# Schematic_Livestock_control_and_monitori.net
KiCad netlist of a schematic drawn in Altium Designer
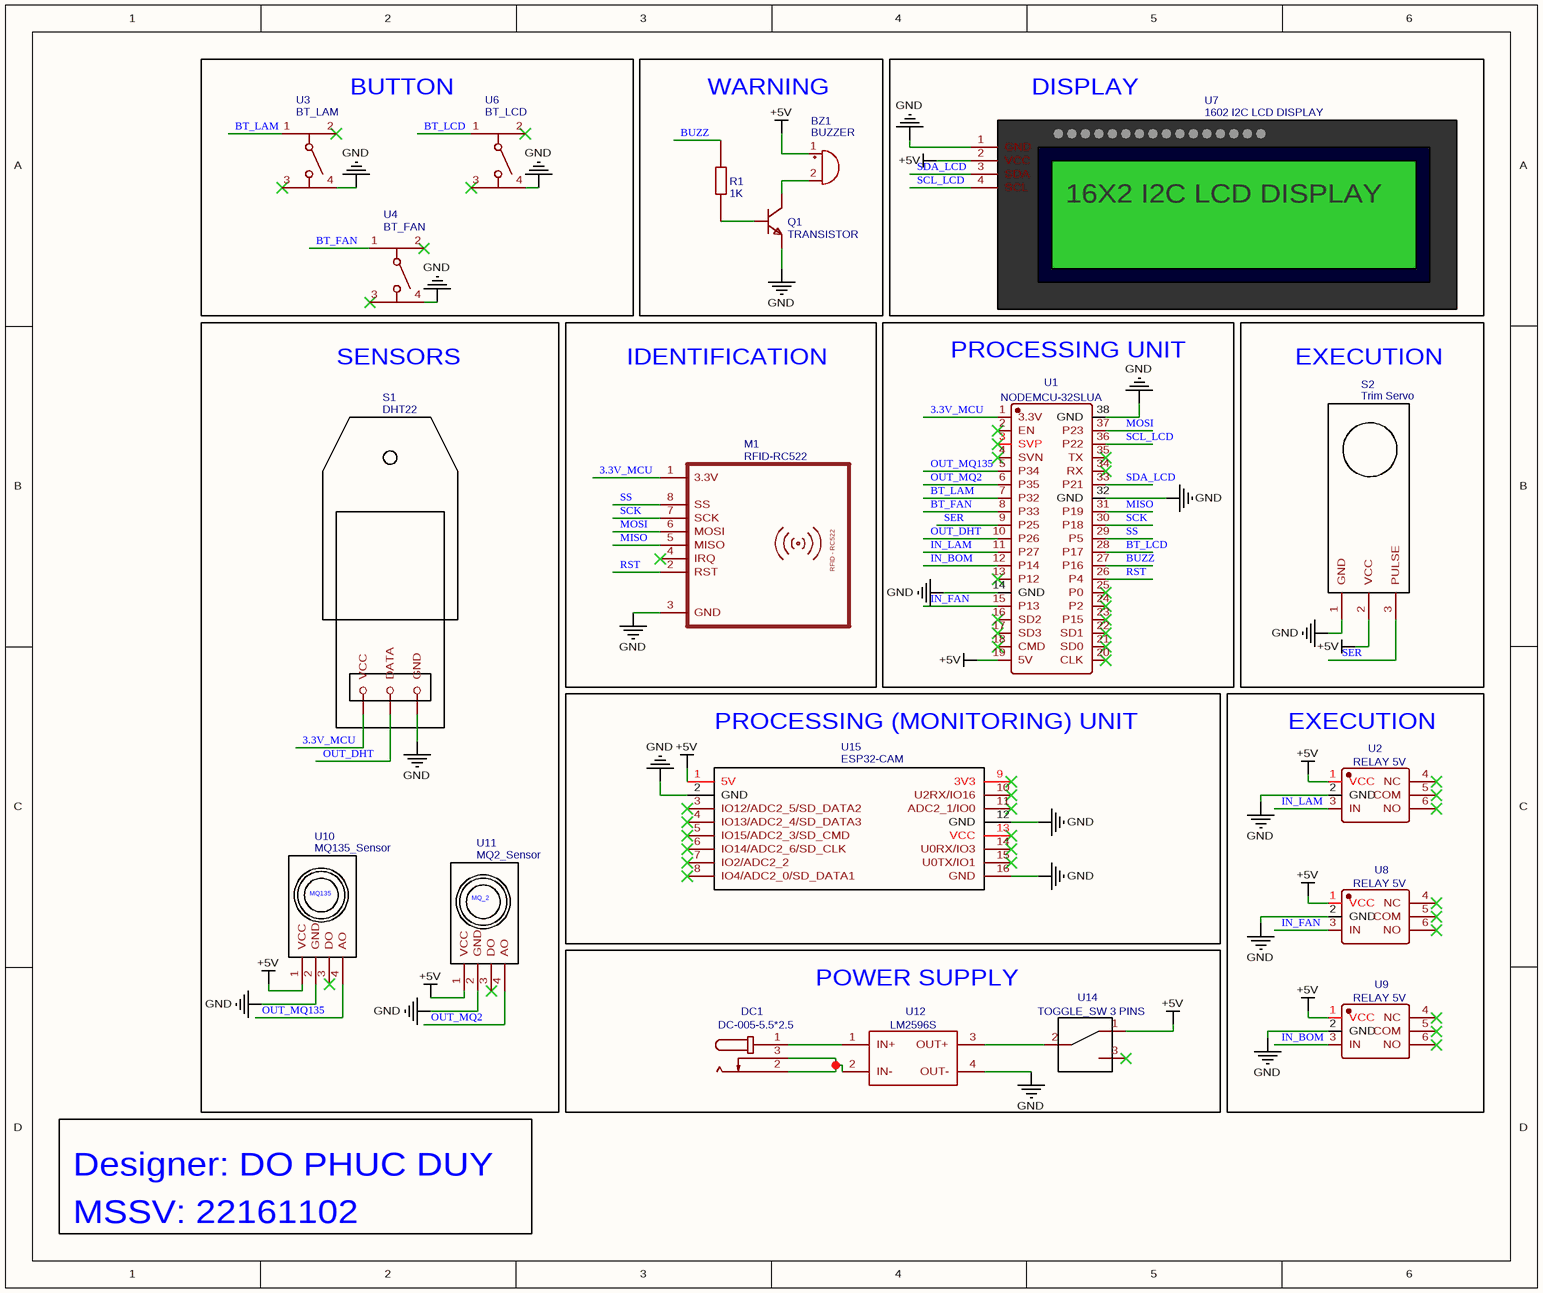
[diagram p0: Schematic_Livestock control and monitoring system.schdoc]

(export (version "E")
  (design (tool "Eeschema 10.0.6"))
  (components
    (comp (ref "BZ1")
      (value "BUZZER")
      (fields (field (name "CONTRIBUTOR") "xuantan27012003"))
      (libsource (lib "altium-import") (part "root_0_BUZZER_"))
    )
    (comp (ref "DC1")
      (value "DC-005-5.5*2.5")
      (fields (field (name "CONTRIBUTOR") "lcsc"))
      (libsource (lib "altium-import") (part "root_0_DC-005-5.5*2.5_"))
    )
    (comp (ref "M1")
      (value "RFID-RC522")
      (fields (field (name "CONTRIBUTOR") "manthan_0182"))
      (libsource (lib "altium-import") (part "root_0_RFID-RC522_"))
    )
    (comp (ref "Q1")
      (value "TRANSISTOR")
      (fields
        (field (name "MANUFACTURER") "SEMTECH")
        (field (name "MANUFACTURER PART") "2N4401")
        (field (name "CONTRIBUTOR") "ali.sivananda")
      )
      (libsource (lib "altium-import") (part "root_0_TRANSISTOR_"))
    )
    (comp (ref "R1")
      (value "1K")
      (fields
        (field (name "MANUFACTURER") "Multicomp")
        (field (name "MANUFACTURER PART") "MOR01SJ0101A10")
        (field (name "CONTRIBUTOR") "Isuru Sandaruwan")
      )
      (libsource (lib "altium-import") (part "root_1_1K_"))
    )
    (comp (ref "S1")
      (value "DHT22")
      (fields (field (name "CONTRIBUTOR") "Muhammad Taufiq"))
      (libsource (lib "altium-import") (part "root_1_DHT22_"))
    )
    (comp (ref "S2")
      (value "Trim Servo")
      (fields (field (name "CONTRIBUTOR") "Sunil Sinsinwar"))
      (libsource (lib "altium-import") (part "root_0_Trim Servo_"))
    )
    (comp (ref "U1")
      (value "NODEMCU-32SLUA")
      (fields
        (field (name "MANUFACTURER") "Ai-Thinker(安信可)")
        (field (name "MANUFACTURER PART") "NodeMCU-32SLua")
        (field (name "CONTRIBUTOR") "lcsc")
      )
      (libsource (lib "altium-import") (part "root_0_NODEMCU-32SLUA_"))
    )
    (comp (ref "U2")
      (value "RELAY 5V")
      (fields
        (field (name "MANUFACTURER") "China")
        (field (name "MANUFACTURER PART") "Monday Kids")
        (field (name "CONTRIBUTOR") "dophucduy3")
      )
      (libsource (lib "altium-import") (part "root_0_RELAY 5V_"))
    )
    (comp (ref "U3")
      (value "BT_LAM")
      (fields
        (field (name "MANUFACTURER") "BBJ")
        (field (name "MANUFACTURER PART") "Switch,6*6*6Plastic head,260G, 0.25mm,Straight line")
      )
      (libsource (lib "altium-import") (part "root_0_BT_LAM_"))
    )
    (comp (ref "U4")
      (value "BT_FAN")
      (fields
        (field (name "MANUFACTURER") "BBJ")
        (field (name "MANUFACTURER PART") "Switch,6*6*6Plastic head,260G, 0.25mm,Straight line")
      )
      (libsource (lib "altium-import") (part "root_0_BT_FAN_"))
    )
    (comp (ref "U6")
      (value "BT_LCD")
      (fields
        (field (name "MANUFACTURER") "BBJ")
        (field (name "MANUFACTURER PART") "Switch,6*6*6Plastic head,260G, 0.25mm,Straight line")
      )
      (libsource (lib "altium-import") (part "root_0_BT_LCD_"))
    )
    (comp (ref "U7")
      (value "1602 I2C LCD DISPLAY")
      (fields (field (name "CONTRIBUTOR") "dophucduy3"))
      (libsource (lib "altium-import") (part "root_0_1602 I2C LCD DISPLAY_"))
    )
    (comp (ref "U8")
      (value "RELAY 5V")
      (fields
        (field (name "MANUFACTURER") "China")
        (field (name "MANUFACTURER PART") "Monday Kids")
        (field (name "CONTRIBUTOR") "dophucduy3")
      )
      (libsource (lib "altium-import") (part "root_0_RELAY 5V_"))
    )
    (comp (ref "U9")
      (value "RELAY 5V")
      (fields
        (field (name "MANUFACTURER") "China")
        (field (name "MANUFACTURER PART") "Monday Kids")
        (field (name "CONTRIBUTOR") "dophucduy3")
      )
      (libsource (lib "altium-import") (part "root_0_RELAY 5V_"))
    )
    (comp (ref "U10")
      (value "MQ135_Sensor")
      (fields (field (name "CONTRIBUTOR") "rusiru5707"))
      (libsource (lib "altium-import") (part "root_0_MQ135_Sensor_"))
    )
    (comp (ref "U11")
      (value "MQ2_Sensor")
      (fields (field (name "CONTRIBUTOR") "rusiru5707"))
      (libsource (lib "altium-import") (part "root_0_MQ2_Sensor_"))
    )
    (comp (ref "U12")
      (value "LM2596S")
      (description "Servo 5V")
      (fields (field (name "CONTRIBUTOR") "mannymoy86"))
      (libsource (lib "altium-import") (part "root_0_LM2596S_"))
    )
    (comp (ref "U14")
      (value "TOGGLE_SW 3 PINS")
      (fields (field (name "CONTRIBUTOR") "cesaro.patafisico"))
      (libsource (lib "altium-import") (part "root_0_TOGGLE_SW 3 PINS_"))
    )
    (comp (ref "U15")
      (value "ESP32-CAM")
      (fields (field (name "CONTRIBUTOR") "dophucduy3"))
      (libsource (lib "altium-import") (part "root_0_ESP32-CAM_"))
    )
  )
  (nets
    (net (code "1") (name "+5V") (class "Default")
      (node (ref "BZ1") (pin "1") (pinfunction "+_1") (pintype "passive"))
      (node (ref "S2") (pin "2") (pinfunction "VCC_2") (pintype "passive"))
      (node (ref "U1") (pin "19") (pinfunction "5V_19") (pintype "passive"))
      (node (ref "U10") (pin "1") (pinfunction "VCC_1") (pintype "passive"))
      (node (ref "U11") (pin "1") (pinfunction "VCC_1") (pintype "passive"))
      (node (ref "U14") (pin "1") (pinfunction "1_1") (pintype "passive"))
      (node (ref "U15") (pin "1") (pinfunction "5V_1") (pintype "passive"))
      (node (ref "U2") (pin "1") (pinfunction "VCC_1") (pintype "passive"))
      (node (ref "U7") (pin "2") (pinfunction "VCC_2") (pintype "passive"))
      (node (ref "U8") (pin "1") (pinfunction "VCC_1") (pintype "passive"))
      (node (ref "U9") (pin "1") (pinfunction "VCC_1") (pintype "passive"))
    )
    (net (code "2") (name "/3.3V_MCU") (class "Default")
      (node (ref "M1") (pin "1") (pinfunction "3.3V_1") (pintype "passive"))
      (node (ref "S1") (pin "1") (pinfunction "VCC_1") (pintype "passive"))
      (node (ref "U1") (pin "1") (pinfunction "3.3V_1") (pintype "passive"))
    )
    (net (code "3") (name "/BT_FAN") (class "Default")
      (node (ref "U1") (pin "8") (pinfunction "P33_8") (pintype "passive"))
      (node (ref "U4") (pin "1") (pinfunction "1_1") (pintype "passive"))
    )
    (net (code "4") (name "/BT_LAM") (class "Default")
      (node (ref "U1") (pin "7") (pinfunction "P32_7") (pintype "passive"))
      (node (ref "U3") (pin "1") (pinfunction "1_1") (pintype "passive"))
    )
    (net (code "5") (name "/BT_LCD") (class "Default")
      (node (ref "U1") (pin "28") (pinfunction "P17_28") (pintype "passive"))
      (node (ref "U6") (pin "1") (pinfunction "1_1") (pintype "passive"))
    )
    (net (code "6") (name "/BUZZ") (class "Default")
      (node (ref "R1") (pin "2") (pinfunction "2_2") (pintype "passive"))
      (node (ref "U1") (pin "27") (pinfunction "P16_27") (pintype "passive"))
    )
    (net (code "7") (name "/IN_BOM") (class "Default")
      (node (ref "U1") (pin "12") (pinfunction "P14_12") (pintype "passive"))
      (node (ref "U9") (pin "3") (pinfunction "IN_3") (pintype "passive"))
    )
    (net (code "8") (name "/IN_FAN") (class "Default")
      (node (ref "U1") (pin "15") (pinfunction "P13_15") (pintype "passive"))
      (node (ref "U8") (pin "3") (pinfunction "IN_3") (pintype "passive"))
    )
    (net (code "9") (name "/IN_LAM") (class "Default")
      (node (ref "U1") (pin "11") (pinfunction "P27_11") (pintype "passive"))
      (node (ref "U2") (pin "3") (pinfunction "IN_3") (pintype "passive"))
    )
    (net (code "10") (name "/MISO") (class "Default")
      (node (ref "M1") (pin "5") (pinfunction "MISO_5") (pintype "passive"))
      (node (ref "U1") (pin "31") (pinfunction "P19_31") (pintype "passive"))
    )
    (net (code "11") (name "/MOSI") (class "Default")
      (node (ref "M1") (pin "6") (pinfunction "MOSI_6") (pintype "passive"))
      (node (ref "U1") (pin "37") (pinfunction "P23_37") (pintype "passive"))
    )
    (net (code "12") (name "/OUT_DHT") (class "Default")
      (node (ref "S1") (pin "2") (pinfunction "DATA_2") (pintype "passive"))
      (node (ref "U1") (pin "10") (pinfunction "P26_10") (pintype "passive"))
    )
    (net (code "13") (name "/OUT_MQ2") (class "Default")
      (node (ref "U1") (pin "6") (pinfunction "P35_6") (pintype "passive"))
      (node (ref "U11") (pin "4") (pinfunction "AO_4") (pintype "passive"))
    )
    (net (code "14") (name "/OUT_MQ135") (class "Default")
      (node (ref "U1") (pin "5") (pinfunction "P34_5") (pintype "passive"))
      (node (ref "U10") (pin "4") (pinfunction "AO_4") (pintype "passive"))
    )
    (net (code "15") (name "/RST") (class "Default")
      (node (ref "M1") (pin "2") (pinfunction "RST_2") (pintype "passive"))
      (node (ref "U1") (pin "26") (pinfunction "P4_26") (pintype "passive"))
    )
    (net (code "16") (name "/SCK") (class "Default")
      (node (ref "M1") (pin "7") (pinfunction "SCK_7") (pintype "passive"))
      (node (ref "U1") (pin "30") (pinfunction "P18_30") (pintype "passive"))
    )
    (net (code "17") (name "/SCL_LCD") (class "Default")
      (node (ref "U1") (pin "36") (pinfunction "P22_36") (pintype "passive"))
      (node (ref "U7") (pin "4") (pinfunction "SCL_4") (pintype "passive"))
    )
    (net (code "18") (name "/SDA_LCD") (class "Default")
      (node (ref "U1") (pin "33") (pinfunction "P21_33") (pintype "passive"))
      (node (ref "U7") (pin "3") (pinfunction "SDA_3") (pintype "passive"))
    )
    (net (code "19") (name "/SER") (class "Default")
      (node (ref "S2") (pin "3") (pinfunction "PULSE_3") (pintype "passive"))
      (node (ref "U1") (pin "9") (pinfunction "P25_9") (pintype "passive"))
    )
    (net (code "20") (name "/SS") (class "Default")
      (node (ref "M1") (pin "8") (pinfunction "SS_8") (pintype "passive"))
      (node (ref "U1") (pin "29") (pinfunction "P5_29") (pintype "passive"))
    )
    (net (code "21") (name "GND") (class "Default")
      (node (ref "M1") (pin "3") (pinfunction "GND_3") (pintype "passive"))
      (node (ref "Q1") (pin "1") (pinfunction "E_1") (pintype "passive"))
      (node (ref "S1") (pin "3") (pinfunction "GND_3") (pintype "passive"))
      (node (ref "S2") (pin "1") (pinfunction "GND_1") (pintype "passive"))
      (node (ref "U1") (pin "14") (pinfunction "GND_14") (pintype "passive"))
      (node (ref "U1") (pin "32") (pinfunction "GND_32") (pintype "passive"))
      (node (ref "U1") (pin "38") (pinfunction "GND_38") (pintype "passive"))
      (node (ref "U10") (pin "2") (pinfunction "GND_2") (pintype "passive"))
      (node (ref "U11") (pin "2") (pinfunction "GND_2") (pintype "passive"))
      (node (ref "U12") (pin "4") (pinfunction "OUT-_4") (pintype "passive"))
      (node (ref "U15") (pin "12") (pinfunction "GND_12") (pintype "passive"))
      (node (ref "U15") (pin "16") (pinfunction "GND_16") (pintype "passive"))
      (node (ref "U15") (pin "2") (pinfunction "GND_2") (pintype "passive"))
      (node (ref "U2") (pin "2") (pinfunction "GND_2") (pintype "passive"))
      (node (ref "U3") (pin "4") (pinfunction "4_4") (pintype "passive"))
      (node (ref "U4") (pin "4") (pinfunction "4_4") (pintype "passive"))
      (node (ref "U6") (pin "4") (pinfunction "4_4") (pintype "passive"))
      (node (ref "U7") (pin "1") (pinfunction "GND_1") (pintype "passive"))
      (node (ref "U8") (pin "2") (pinfunction "GND_2") (pintype "passive"))
      (node (ref "U9") (pin "2") (pinfunction "GND_2") (pintype "passive"))
    )
    (net (code "22") (name "Net-(BZ1--)") (class "Default")
      (node (ref "BZ1") (pin "2") (pinfunction "-_2") (pintype "passive"))
      (node (ref "Q1") (pin "3") (pinfunction "C_3") (pintype "passive"))
    )
    (net (code "23") (name "Net-(Q1-B)") (class "Default")
      (node (ref "Q1") (pin "2") (pinfunction "B_2") (pintype "passive"))
      (node (ref "R1") (pin "1") (pinfunction "1_1") (pintype "passive"))
    )
    (net (code "24") (name "Net-(U12-IN+)") (class "Default")
      (node (ref "DC1") (pin "1") (pinfunction "1_1") (pintype "passive"))
      (node (ref "U12") (pin "1") (pinfunction "IN+_1") (pintype "passive"))
    )
    (net (code "25") (name "Net-(U12-IN-)") (class "Default")
      (node (ref "DC1") (pin "2") (pinfunction "2_2") (pintype "passive"))
      (node (ref "DC1") (pin "3") (pinfunction "3_3") (pintype "passive"))
      (node (ref "U12") (pin "2") (pinfunction "IN-_2") (pintype "passive"))
    )
    (net (code "26") (name "Net-(U12-OUT+)") (class "Default")
      (node (ref "U12") (pin "3") (pinfunction "OUT+_3") (pintype "passive"))
      (node (ref "U14") (pin "2") (pinfunction "2_2") (pintype "passive"))
    )
    (net (code "27") (name "unconnected-(M1-IRQ-Pad4)") (class "Default")
      (node (ref "M1") (pin "4") (pinfunction "IRQ_4") (pintype "passive+no_connect"))
    )
    (net (code "28") (name "unconnected-(U1-CLK-Pad20)") (class "Default")
      (node (ref "U1") (pin "20") (pinfunction "CLK_20") (pintype "passive+no_connect"))
    )
    (net (code "29") (name "unconnected-(U1-CMD-Pad18)") (class "Default")
      (node (ref "U1") (pin "18") (pinfunction "CMD_18") (pintype "passive+no_connect"))
    )
    (net (code "30") (name "unconnected-(U1-EN-Pad2)") (class "Default")
      (node (ref "U1") (pin "2") (pinfunction "EN_2") (pintype "passive+no_connect"))
    )
    (net (code "31") (name "unconnected-(U1-P0-Pad25)") (class "Default")
      (node (ref "U1") (pin "25") (pinfunction "P0_25") (pintype "passive+no_connect"))
    )
    (net (code "32") (name "unconnected-(U1-P2-Pad24)") (class "Default")
      (node (ref "U1") (pin "24") (pinfunction "P2_24") (pintype "passive+no_connect"))
    )
    (net (code "33") (name "unconnected-(U1-P12-Pad13)") (class "Default")
      (node (ref "U1") (pin "13") (pinfunction "P12_13") (pintype "passive+no_connect"))
    )
    (net (code "34") (name "unconnected-(U1-P15-Pad23)") (class "Default")
      (node (ref "U1") (pin "23") (pinfunction "P15_23") (pintype "passive+no_connect"))
    )
    (net (code "35") (name "unconnected-(U1-RX-Pad34)") (class "Default")
      (node (ref "U1") (pin "34") (pinfunction "RX_34") (pintype "passive+no_connect"))
    )
    (net (code "36") (name "unconnected-(U1-SD0-Pad21)") (class "Default")
      (node (ref "U1") (pin "21") (pinfunction "SD0_21") (pintype "passive+no_connect"))
    )
    (net (code "37") (name "unconnected-(U1-SD1-Pad22)") (class "Default")
      (node (ref "U1") (pin "22") (pinfunction "SD1_22") (pintype "passive+no_connect"))
    )
    (net (code "38") (name "unconnected-(U1-SD2-Pad16)") (class "Default")
      (node (ref "U1") (pin "16") (pinfunction "SD2_16") (pintype "passive+no_connect"))
    )
    (net (code "39") (name "unconnected-(U1-SD3-Pad17)") (class "Default")
      (node (ref "U1") (pin "17") (pinfunction "SD3_17") (pintype "passive+no_connect"))
    )
    (net (code "40") (name "unconnected-(U1-SVN-Pad4)") (class "Default")
      (node (ref "U1") (pin "4") (pinfunction "SVN_4") (pintype "passive+no_connect"))
    )
    (net (code "41") (name "unconnected-(U1-SVP-Pad3)") (class "Default")
      (node (ref "U1") (pin "3") (pinfunction "SVP_3") (pintype "passive+no_connect"))
    )
    (net (code "42") (name "unconnected-(U1-TX-Pad35)") (class "Default")
      (node (ref "U1") (pin "35") (pinfunction "TX_35") (pintype "passive+no_connect"))
    )
    (net (code "43") (name "unconnected-(U2-COM-Pad5)") (class "Default")
      (node (ref "U2") (pin "5") (pinfunction "COM_5") (pintype "passive+no_connect"))
    )
    (net (code "44") (name "unconnected-(U2-NC-Pad4)") (class "Default")
      (node (ref "U2") (pin "4") (pinfunction "NC_4") (pintype "passive+no_connect"))
    )
    (net (code "45") (name "unconnected-(U2-NO-Pad6)") (class "Default")
      (node (ref "U2") (pin "6") (pinfunction "NO_6") (pintype "passive+no_connect"))
    )
    (net (code "46") (name "unconnected-(U3-Pad2)") (class "Default")
      (node (ref "U3") (pin "2") (pinfunction "2_2") (pintype "passive+no_connect"))
    )
    (net (code "47") (name "unconnected-(U3-Pad3)") (class "Default")
      (node (ref "U3") (pin "3") (pinfunction "3_3") (pintype "passive+no_connect"))
    )
    (net (code "48") (name "unconnected-(U4-Pad2)") (class "Default")
      (node (ref "U4") (pin "2") (pinfunction "2_2") (pintype "passive+no_connect"))
    )
    (net (code "49") (name "unconnected-(U4-Pad3)") (class "Default")
      (node (ref "U4") (pin "3") (pinfunction "3_3") (pintype "passive+no_connect"))
    )
    (net (code "50") (name "unconnected-(U6-Pad2)") (class "Default")
      (node (ref "U6") (pin "2") (pinfunction "2_2") (pintype "passive+no_connect"))
    )
    (net (code "51") (name "unconnected-(U6-Pad3)") (class "Default")
      (node (ref "U6") (pin "3") (pinfunction "3_3") (pintype "passive+no_connect"))
    )
    (net (code "52") (name "unconnected-(U8-COM-Pad5)") (class "Default")
      (node (ref "U8") (pin "5") (pinfunction "COM_5") (pintype "passive+no_connect"))
    )
    (net (code "53") (name "unconnected-(U8-NC-Pad4)") (class "Default")
      (node (ref "U8") (pin "4") (pinfunction "NC_4") (pintype "passive+no_connect"))
    )
    (net (code "54") (name "unconnected-(U8-NO-Pad6)") (class "Default")
      (node (ref "U8") (pin "6") (pinfunction "NO_6") (pintype "passive+no_connect"))
    )
    (net (code "55") (name "unconnected-(U9-COM-Pad5)") (class "Default")
      (node (ref "U9") (pin "5") (pinfunction "COM_5") (pintype "passive+no_connect"))
    )
    (net (code "56") (name "unconnected-(U9-NC-Pad4)") (class "Default")
      (node (ref "U9") (pin "4") (pinfunction "NC_4") (pintype "passive+no_connect"))
    )
    (net (code "57") (name "unconnected-(U9-NO-Pad6)") (class "Default")
      (node (ref "U9") (pin "6") (pinfunction "NO_6") (pintype "passive+no_connect"))
    )
    (net (code "58") (name "unconnected-(U10-DO-Pad3)") (class "Default")
      (node (ref "U10") (pin "3") (pinfunction "DO_3") (pintype "passive+no_connect"))
    )
    (net (code "59") (name "unconnected-(U11-DO-Pad3)") (class "Default")
      (node (ref "U11") (pin "3") (pinfunction "DO_3") (pintype "passive+no_connect"))
    )
    (net (code "60") (name "unconnected-(U14-Pad3)") (class "Default")
      (node (ref "U14") (pin "3") (pinfunction "3_3") (pintype "passive+no_connect"))
    )
    (net (code "61") (name "unconnected-(U15-3V3-Pad9)") (class "Default")
      (node (ref "U15") (pin "9") (pinfunction "3V3_9") (pintype "passive+no_connect"))
    )
    (net (code "62") (name "unconnected-(U15-ADC2_1{slash}IO0-Pad11)") (class "Default")
      (node (ref "U15") (pin "11") (pinfunction "ADC2_1/IO0_11") (pintype "passive+no_connect"))
    )
    (net (code "63") (name "unconnected-(U15-IO2{slash}ADC2_2-Pad7)") (class "Default")
      (node (ref "U15") (pin "7") (pinfunction "IO2/ADC2_2_7") (pintype "passive+no_connect"))
    )
    (net (code "64") (name "unconnected-(U15-IO4{slash}ADC2_0{slash}SD_DATA1-Pad8)") (class "Default")
      (node (ref "U15") (pin "8") (pinfunction "IO4/ADC2_0/SD_DATA1_8") (pintype "passive+no_connect"))
    )
    (net (code "65") (name "unconnected-(U15-IO12{slash}ADC2_5{slash}SD_DATA2-Pad3)") (class "Default")
      (node (ref "U15") (pin "3") (pinfunction "IO12/ADC2_5/SD_DATA2_3") (pintype "passive+no_connect"))
    )
    (net (code "66") (name "unconnected-(U15-IO13{slash}ADC2_4{slash}SD_DATA3-Pad4)") (class "Default")
      (node (ref "U15") (pin "4") (pinfunction "IO13/ADC2_4/SD_DATA3_4") (pintype "passive+no_connect"))
    )
    (net (code "67") (name "unconnected-(U15-IO14{slash}ADC2_6{slash}SD_CLK-Pad6)") (class "Default")
      (node (ref "U15") (pin "6") (pinfunction "IO14/ADC2_6/SD_CLK_6") (pintype "passive+no_connect"))
    )
    (net (code "68") (name "unconnected-(U15-IO15{slash}ADC2_3{slash}SD_CMD-Pad5)") (class "Default")
      (node (ref "U15") (pin "5") (pinfunction "IO15/ADC2_3/SD_CMD_5") (pintype "passive+no_connect"))
    )
    (net (code "69") (name "unconnected-(U15-U0RX{slash}IO3-Pad14)") (class "Default")
      (node (ref "U15") (pin "14") (pinfunction "U0RX/IO3_14") (pintype "passive+no_connect"))
    )
    (net (code "70") (name "unconnected-(U15-U0TX{slash}IO1-Pad15)") (class "Default")
      (node (ref "U15") (pin "15") (pinfunction "U0TX/IO1_15") (pintype "passive+no_connect"))
    )
    (net (code "71") (name "unconnected-(U15-U2RX{slash}IO16-Pad10)") (class "Default")
      (node (ref "U15") (pin "10") (pinfunction "U2RX/IO16_10") (pintype "passive+no_connect"))
    )
    (net (code "72") (name "unconnected-(U15-VCC-Pad13)") (class "Default")
      (node (ref "U15") (pin "13") (pinfunction "VCC_13") (pintype "passive+no_connect"))
    )
  )
)
